# auto.net
KiCad netlist of a schematic drawn in EAGLE
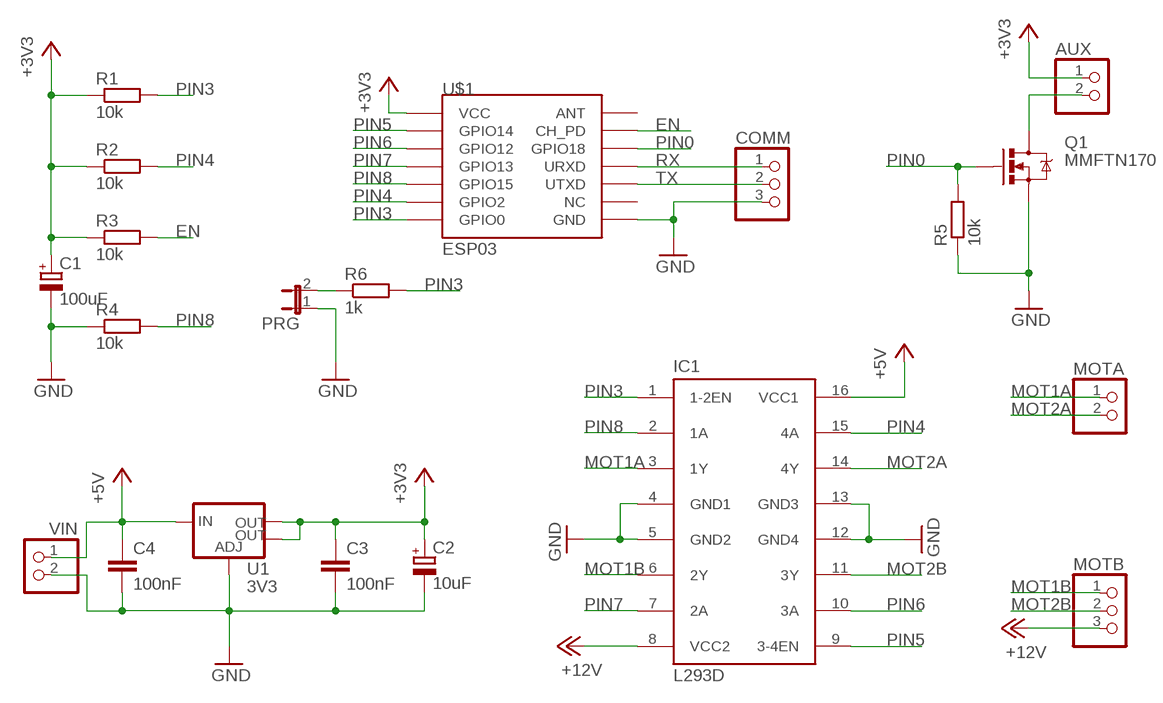
[diagram p0: schematic, sheet 1]

(export (version "E")
  (design (tool "Eeschema 10.0.6"))
  (components
    (comp (ref "AUX")
      (value "PINHD-1X2")
      (footprint "eagle-import:1X02")
      (libsource (lib "eagle-import") (part "PINHD-1X2"))
    )
    (comp (ref "C1")
      (value "100uF")
      (footprint "eagle-import:E2,5-5")
      (libsource (lib "eagle-import") (part "CPOL-EUE2.5-5"))
    )
    (comp (ref "C2")
      (value "10uF")
      (footprint "eagle-import:E2,5-5")
      (libsource (lib "eagle-import") (part "CPOL-EUE2.5-5"))
    )
    (comp (ref "C3")
      (value "100nF")
      (footprint "eagle-import:C1206")
      (libsource (lib "eagle-import") (part "C-EUC1206"))
    )
    (comp (ref "C4")
      (value "100nF")
      (footprint "eagle-import:C1206")
      (libsource (lib "eagle-import") (part "C-EUC1206"))
    )
    (comp (ref "COMM")
      (value "PINHD-1X3")
      (footprint "eagle-import:1X03")
      (libsource (lib "eagle-import") (part "PINHD-1X3"))
    )
    (comp (ref "IC1")
      (value "L293D")
      (footprint "eagle-import:DIL16")
      (libsource (lib "eagle-import") (part "L293D"))
    )
    (comp (ref "MOTA")
      (value "PINHD-1X2")
      (footprint "eagle-import:1X02")
      (libsource (lib "eagle-import") (part "PINHD-1X2"))
    )
    (comp (ref "MOTB")
      (value "PINHD-1X3")
      (footprint "eagle-import:1X03")
      (libsource (lib "eagle-import") (part "PINHD-1X3"))
    )
    (comp (ref "PRG")
      (value "JP1E")
      (footprint "eagle-import:JP1")
      (libsource (lib "eagle-import") (part "JP1E"))
    )
    (comp (ref "Q1")
      (value "MMFTN170")
      (footprint "eagle-import:SOT23-3")
      (libsource (lib "eagle-import") (part "MOSFET-NCHANNELAO3404A"))
    )
    (comp (ref "R1")
      (value "10k")
      (footprint "eagle-import:R0805")
      (libsource (lib "eagle-import") (part "R-EU_R0805"))
    )
    (comp (ref "R2")
      (value "10k")
      (footprint "eagle-import:R0805")
      (libsource (lib "eagle-import") (part "R-EU_R0805"))
    )
    (comp (ref "R3")
      (value "10k")
      (footprint "eagle-import:R0805")
      (libsource (lib "eagle-import") (part "R-EU_R0805"))
    )
    (comp (ref "R4")
      (value "10k")
      (footprint "eagle-import:R0805")
      (libsource (lib "eagle-import") (part "R-EU_R0805"))
    )
    (comp (ref "R5")
      (value "10k")
      (footprint "eagle-import:R0805")
      (libsource (lib "eagle-import") (part "R-EU_R0805"))
    )
    (comp (ref "R6")
      (value "1k")
      (footprint "eagle-import:R0805")
      (libsource (lib "eagle-import") (part "R-EU_R0805"))
    )
    (comp (ref "U$1")
      (value "ESP03")
      (footprint "eagle-import:ESP03")
      (libsource (lib "eagle-import") (part "ESP03"))
    )
    (comp (ref "U1")
      (value "3V3")
      (footprint "eagle-import:SOT223")
      (libsource (lib "eagle-import") (part "V_REG_LM1117SOT223"))
    )
    (comp (ref "VIN")
      (value "PINHD-1X2")
      (footprint "eagle-import:1X02")
      (libsource (lib "eagle-import") (part "PINHD-1X2"))
    )
  )
  (nets
    (net (code "1") (name "+3V3") (class "Default")
      (node (ref "AUX") (pin "1") (pinfunction "1_1") (pintype "passive"))
      (node (ref "C1") (pin "+") (pinfunction "+_+") (pintype "passive"))
      (node (ref "C2") (pin "+") (pinfunction "+_+") (pintype "passive"))
      (node (ref "C3") (pin "1") (pinfunction "1_1") (pintype "passive"))
      (node (ref "R1") (pin "1") (pinfunction "1_1") (pintype "passive"))
      (node (ref "R2") (pin "1") (pinfunction "1_1") (pintype "passive"))
      (node (ref "R3") (pin "1") (pinfunction "1_1") (pintype "passive"))
      (node (ref "U$1") (pin "VCC") (pinfunction "VCC_VCC") (pintype "bidirectional"))
      (node (ref "U1") (pin "2") (pinfunction "OUT_2") (pintype "output"))
      (node (ref "U1") (pin "4") (pinfunction "OUT_4") (pintype "output"))
    )
    (net (code "2") (name "+5V") (class "Default")
      (node (ref "C4") (pin "1") (pinfunction "1_1") (pintype "passive"))
      (node (ref "IC1") (pin "16") (pinfunction "VCC1_16") (pintype "power_in"))
      (node (ref "U1") (pin "3") (pinfunction "IN_3") (pintype "input"))
      (node (ref "VIN") (pin "1") (pinfunction "1_1") (pintype "passive"))
    )
    (net (code "3") (name "+12V") (class "Default")
      (node (ref "IC1") (pin "8") (pinfunction "VCC2_8") (pintype "power_in"))
      (node (ref "MOTB") (pin "3") (pinfunction "3_3") (pintype "passive"))
    )
    (net (code "4") (name "/EN") (class "Default")
      (node (ref "R3") (pin "2") (pinfunction "2_2") (pintype "passive"))
      (node (ref "U$1") (pin "CH_PD") (pinfunction "CH_PD_CH_PD") (pintype "bidirectional"))
    )
    (net (code "5") (name "/MOT1A") (class "Default")
      (node (ref "IC1") (pin "3") (pinfunction "1Y_3") (pintype "output"))
      (node (ref "MOTA") (pin "1") (pinfunction "1_1") (pintype "passive"))
    )
    (net (code "6") (name "/MOT1B") (class "Default")
      (node (ref "IC1") (pin "6") (pinfunction "2Y_6") (pintype "output"))
      (node (ref "MOTB") (pin "1") (pinfunction "1_1") (pintype "passive"))
    )
    (net (code "7") (name "/MOT2A") (class "Default")
      (node (ref "IC1") (pin "14") (pinfunction "4Y_14") (pintype "output"))
      (node (ref "MOTA") (pin "2") (pinfunction "2_2") (pintype "passive"))
    )
    (net (code "8") (name "/MOT2B") (class "Default")
      (node (ref "IC1") (pin "11") (pinfunction "3Y_11") (pintype "output"))
      (node (ref "MOTB") (pin "2") (pinfunction "2_2") (pintype "passive"))
    )
    (net (code "9") (name "/PIN0") (class "Default")
      (node (ref "Q1") (pin "1") (pinfunction "G_1") (pintype "passive"))
      (node (ref "R5") (pin "2") (pinfunction "2_2") (pintype "passive"))
      (node (ref "U$1") (pin "GPIO18") (pinfunction "GPIO18_GPIO18") (pintype "bidirectional"))
    )
    (net (code "10") (name "/PIN3") (class "Default")
      (node (ref "IC1") (pin "1") (pinfunction "1-2EN_1") (pintype "input"))
      (node (ref "R1") (pin "2") (pinfunction "2_2") (pintype "passive"))
      (node (ref "R6") (pin "2") (pinfunction "2_2") (pintype "passive"))
      (node (ref "U$1") (pin "GPIO0") (pinfunction "GPIO0_GPIO0") (pintype "bidirectional"))
    )
    (net (code "11") (name "/PIN4") (class "Default")
      (node (ref "IC1") (pin "15") (pinfunction "4A_15") (pintype "input"))
      (node (ref "R2") (pin "2") (pinfunction "2_2") (pintype "passive"))
      (node (ref "U$1") (pin "GPIO2") (pinfunction "GPIO2_GPIO2") (pintype "bidirectional"))
    )
    (net (code "12") (name "/PIN5") (class "Default")
      (node (ref "IC1") (pin "9") (pinfunction "3-4EN_9") (pintype "input"))
      (node (ref "U$1") (pin "GPIO14") (pinfunction "GPIO14_GPIO14") (pintype "bidirectional"))
    )
    (net (code "13") (name "/PIN6") (class "Default")
      (node (ref "IC1") (pin "10") (pinfunction "3A_10") (pintype "input"))
      (node (ref "U$1") (pin "GPIO12") (pinfunction "GPIO12_GPIO12") (pintype "bidirectional"))
    )
    (net (code "14") (name "/PIN7") (class "Default")
      (node (ref "IC1") (pin "7") (pinfunction "2A_7") (pintype "input"))
      (node (ref "U$1") (pin "GPIO13") (pinfunction "GPIO13_GPIO13") (pintype "bidirectional"))
    )
    (net (code "15") (name "/PIN8") (class "Default")
      (node (ref "IC1") (pin "2") (pinfunction "1A_2") (pintype "input"))
      (node (ref "R4") (pin "2") (pinfunction "2_2") (pintype "passive"))
      (node (ref "U$1") (pin "GPIO15") (pinfunction "GPIO15_GPIO15") (pintype "bidirectional"))
    )
    (net (code "16") (name "/RX") (class "Default")
      (node (ref "COMM") (pin "1") (pinfunction "1_1") (pintype "passive"))
      (node (ref "U$1") (pin "URXD") (pinfunction "URXD_URXD") (pintype "bidirectional"))
    )
    (net (code "17") (name "/TX") (class "Default")
      (node (ref "COMM") (pin "2") (pinfunction "2_2") (pintype "passive"))
      (node (ref "U$1") (pin "UTXD") (pinfunction "UTXD_UTXD") (pintype "bidirectional"))
    )
    (net (code "18") (name "GND") (class "Default")
      (node (ref "C1") (pin "-") (pinfunction "-_-") (pintype "passive"))
      (node (ref "C2") (pin "-") (pinfunction "-_-") (pintype "passive"))
      (node (ref "C3") (pin "2") (pinfunction "2_2") (pintype "passive"))
      (node (ref "C4") (pin "2") (pinfunction "2_2") (pintype "passive"))
      (node (ref "COMM") (pin "3") (pinfunction "3_3") (pintype "passive"))
      (node (ref "IC1") (pin "12") (pinfunction "GND4_12") (pintype "power_in"))
      (node (ref "IC1") (pin "13") (pinfunction "GND3_13") (pintype "power_in"))
      (node (ref "IC1") (pin "4") (pinfunction "GND1_4") (pintype "power_in"))
      (node (ref "IC1") (pin "5") (pinfunction "GND2_5") (pintype "power_in"))
      (node (ref "PRG") (pin "1") (pinfunction "1_1") (pintype "passive"))
      (node (ref "Q1") (pin "2") (pinfunction "S_2") (pintype "passive"))
      (node (ref "R4") (pin "1") (pinfunction "1_1") (pintype "passive"))
      (node (ref "R5") (pin "1") (pinfunction "1_1") (pintype "passive"))
      (node (ref "U$1") (pin "GND") (pinfunction "GND_GND") (pintype "bidirectional"))
      (node (ref "U1") (pin "1") (pinfunction "ADJ_1") (pintype "input"))
      (node (ref "VIN") (pin "2") (pinfunction "2_2") (pintype "passive"))
    )
    (net (code "19") (name "Net-(PRG-Pad2)") (class "Default")
      (node (ref "PRG") (pin "2") (pinfunction "2_2") (pintype "passive"))
      (node (ref "R6") (pin "1") (pinfunction "1_1") (pintype "passive"))
    )
    (net (code "20") (name "Net-(Q1-D)") (class "Default")
      (node (ref "AUX") (pin "2") (pinfunction "2_2") (pintype "passive"))
      (node (ref "Q1") (pin "3") (pinfunction "D_3") (pintype "passive"))
    )
    (net (code "21") (name "unconnected-(U$1-PadANT)") (class "Default")
      (node (ref "U$1") (pin "ANT") (pinfunction "ANT_ANT") (pintype "bidirectional"))
    )
    (net (code "22") (name "unconnected-(U$1-PadNC)") (class "Default")
      (node (ref "U$1") (pin "NC") (pinfunction "NC_NC") (pintype "bidirectional"))
    )
  )
)
